# 1-Schematic_trashthingie.net
KiCad netlist of a schematic drawn in EasyEDA
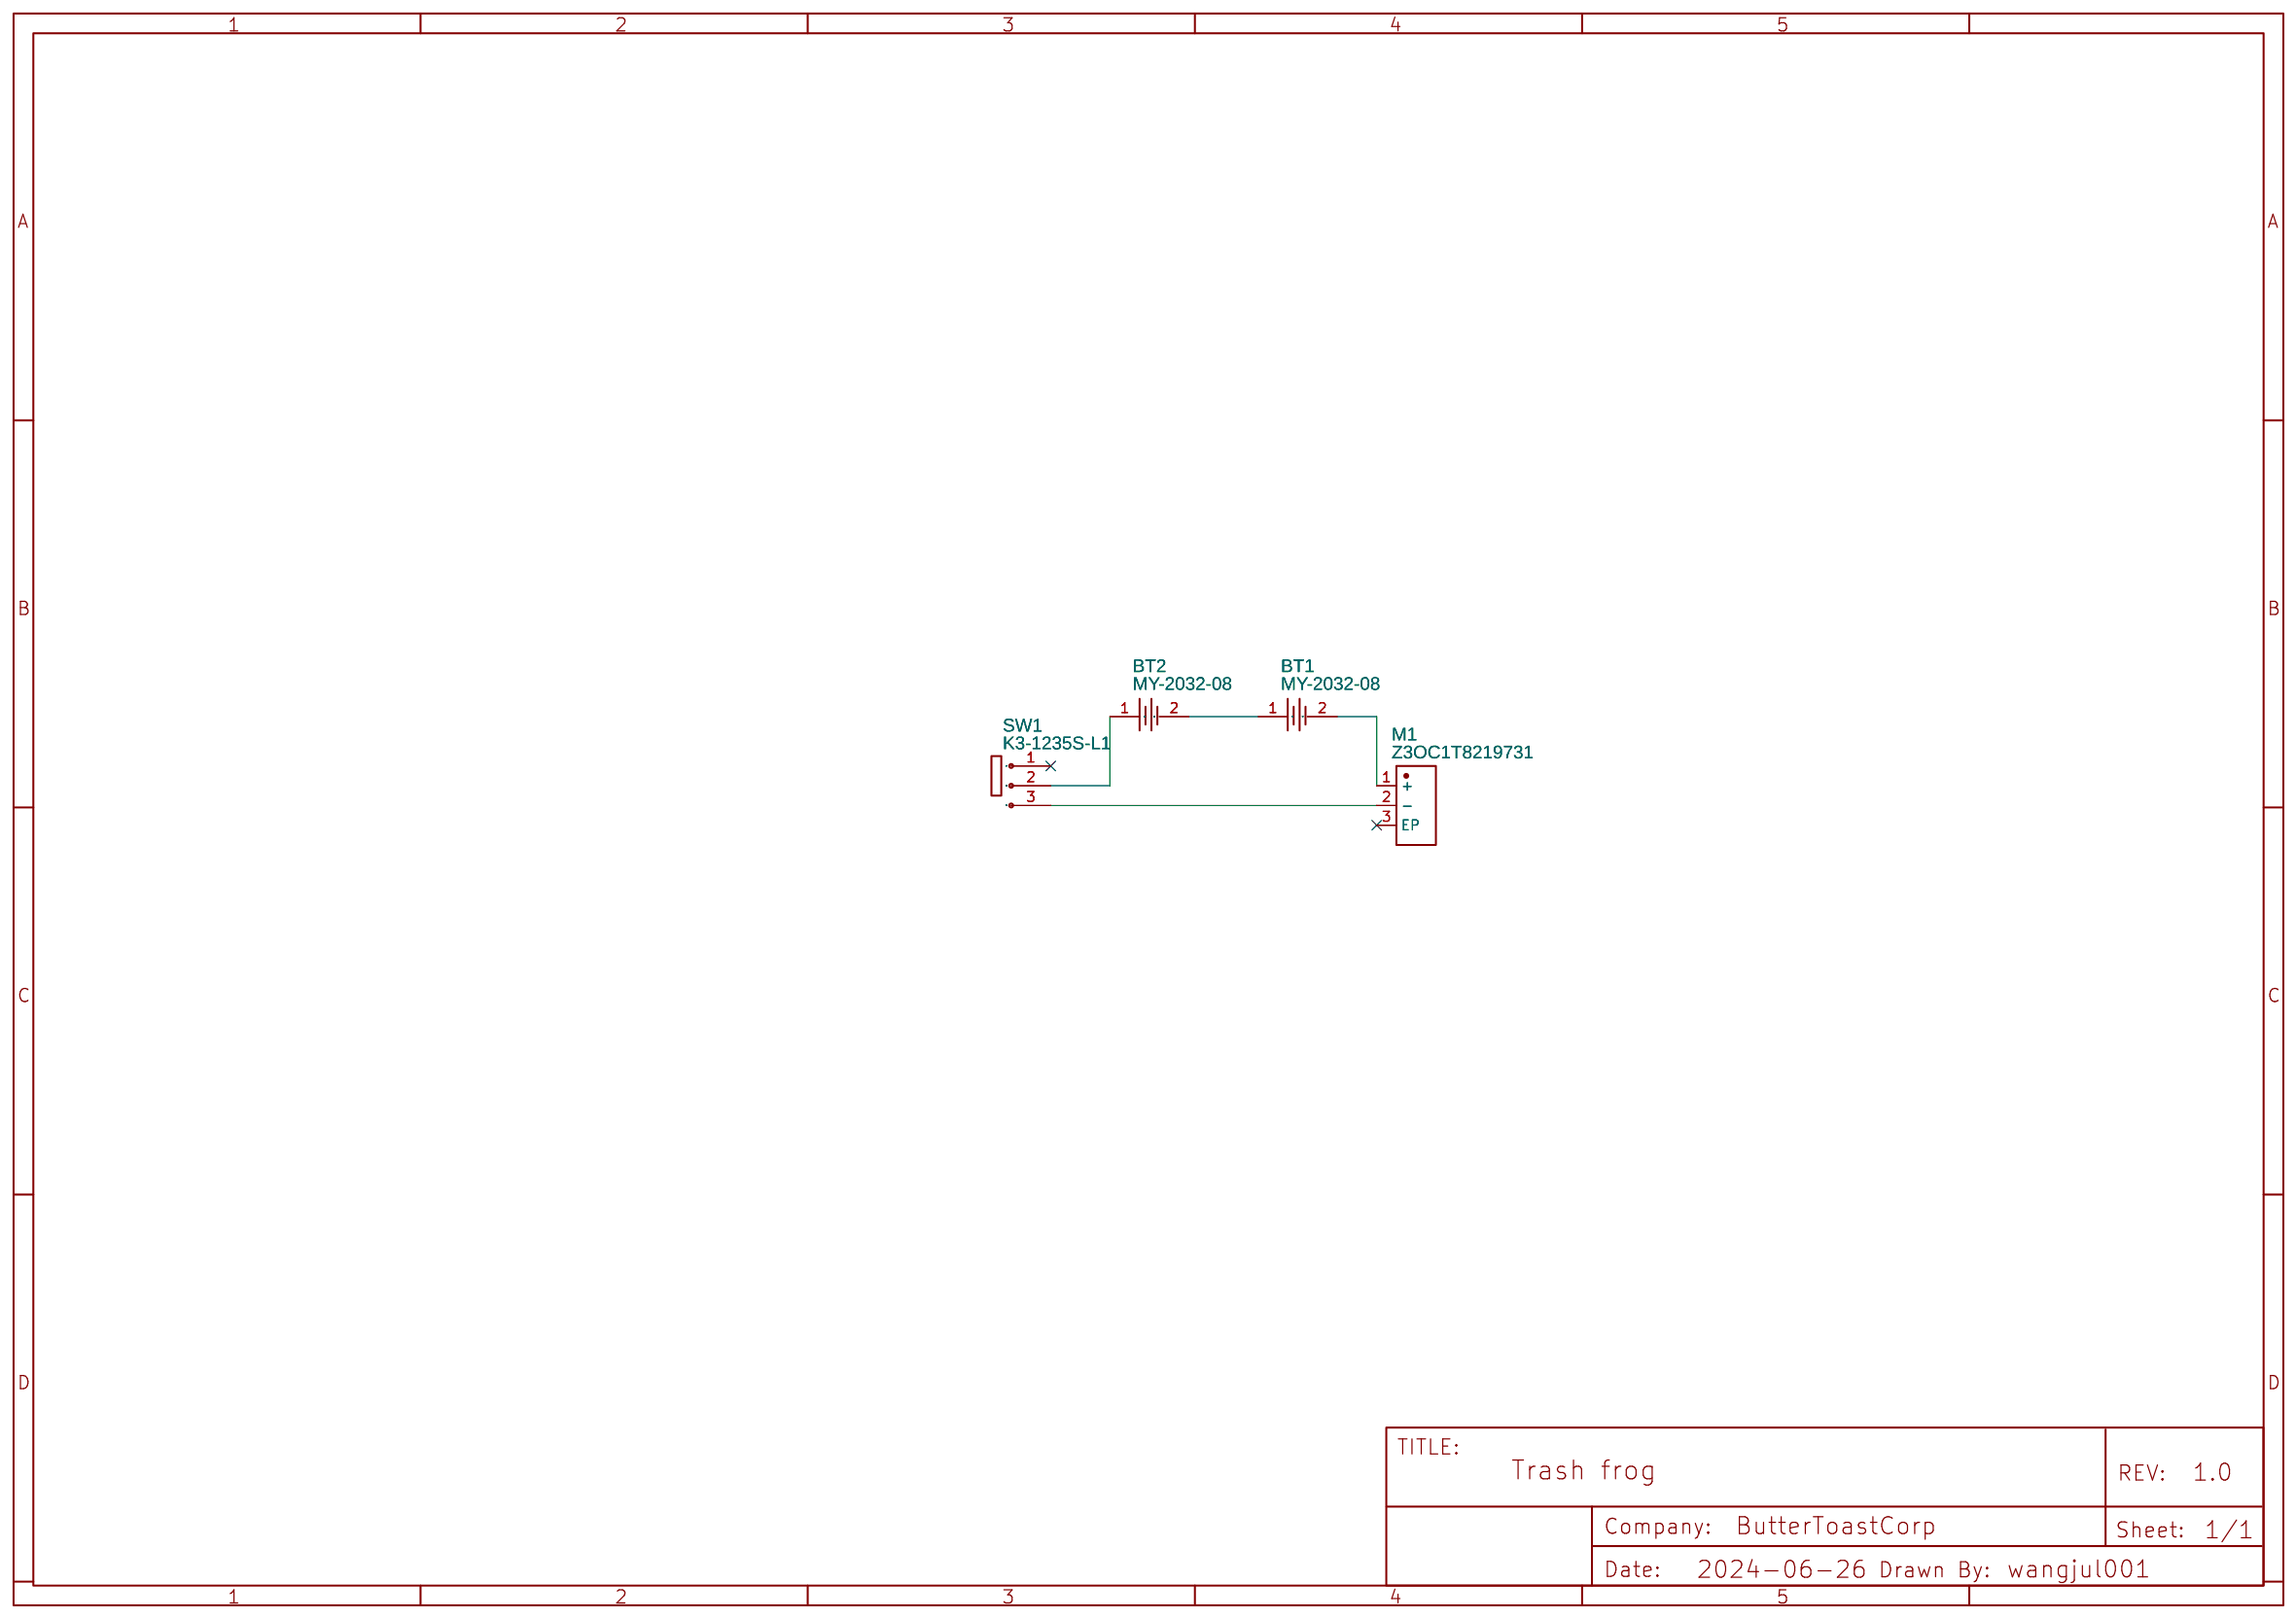
[diagram p0: schematic sheet]

(export (version "E")
  (design (tool "Eeschema 10.0.6"))
  (components
    (comp (ref "BT1")
      (value "MY-2032-08")
      (fields (field (name "Manufacturer") "MYOUNG(美阳)"))
      (libsource (lib "") (part "MY-2032-08"))
    )
    (comp (ref "BT2")
      (value "MY-2032-08")
      (fields (field (name "Manufacturer") "MYOUNG(美阳)"))
      (libsource (lib "") (part "MY-2032-08"))
    )
    (comp (ref "M1")
      (value "Z3OC1T8219731")
      (fields (field (name "Manufacturer") "KOTL(金龙机电)"))
      (libsource (lib "") (part "Z3OC1T8219731"))
    )
    (comp (ref "SW1")
      (value "K3-1235S-L1")
      (fields (field (name "Manufacturer") "韩国韩荣"))
      (libsource (lib "") (part "K3-1235S-L1"))
    )
  )
  (nets
    (net (code "1") (name "Net-(BT1-Pad1)") (class "Default")
      (node (ref "BT1") (pin "1") (pinfunction "1_1") (pintype "input"))
      (node (ref "BT2") (pin "2") (pinfunction "2_2") (pintype "input"))
    )
    (net (code "2") (name "Net-(BT2-Pad1)") (class "Default")
      (node (ref "BT2") (pin "1") (pinfunction "1_1") (pintype "input"))
      (node (ref "SW1") (pin "2") (pinfunction "2_2") (pintype "unspecified"))
    )
    (net (code "3") (name "Net-(M1-+)") (class "Default")
      (node (ref "BT1") (pin "2") (pinfunction "2_2") (pintype "input"))
      (node (ref "M1") (pin "1") (pinfunction "+_1") (pintype "unspecified"))
    )
    (net (code "4") (name "Net-(M1--)") (class "Default")
      (node (ref "M1") (pin "2") (pinfunction "-_2") (pintype "unspecified"))
      (node (ref "SW1") (pin "3") (pinfunction "3_3") (pintype "unspecified"))
    )
    (net (code "5") (name "unconnected-(M1-EP-Pad3)") (class "Default")
      (node (ref "M1") (pin "3") (pinfunction "EP_3") (pintype "unspecified+no_connect"))
    )
    (net (code "6") (name "unconnected-(SW1-Pad1)") (class "Default")
      (node (ref "SW1") (pin "1") (pinfunction "1_1") (pintype "unspecified+no_connect"))
    )
  )
)
